# TCA0372_x.net
KiCad netlist of a schematic drawn in EAGLE
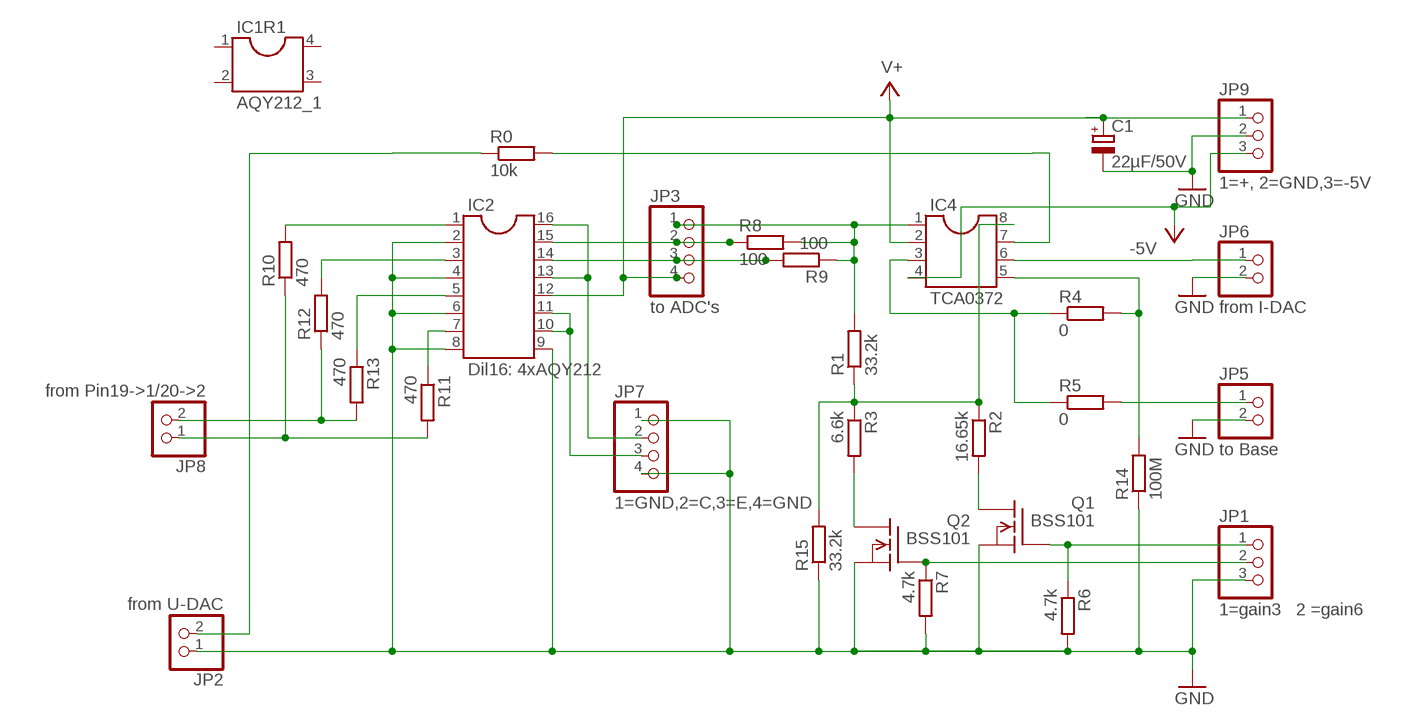
[diagram p0: schematic, sheet 1]

(export (version "E")
  (design (tool "Eeschema 10.0.6"))
  (components
    (comp (ref "C1")
      (value "22µF/50V")
      (footprint "eagle-import:E5-10,5")
      (libsource (lib "eagle-import") (part "CPOL-EUE5-10.5"))
    )
    (comp (ref "IC1R1")
      (value "AQY212_1")
      (footprint "eagle-import:SOCKET-04")
      (libsource (lib "eagle-import") (part "DIL4S"))
    )
    (comp (ref "IC2")
      (value "Dil16: 4xAQY212")
      (footprint "eagle-import:SOCKET-16")
      (libsource (lib "eagle-import") (part "DIL16S"))
    )
    (comp (ref "IC4")
      (value "TCA0372")
      (footprint "eagle-import:SOCKET-08")
      (libsource (lib "eagle-import") (part "DIL8S"))
    )
    (comp (ref "JP1")
      (value "1=gain3 2 =gain6")
      (footprint "eagle-import:1X03")
      (libsource (lib "eagle-import") (part "PINHD-1X3"))
    )
    (comp (ref "JP2")
      (value "from U-DAC")
      (footprint "eagle-import:1X02")
      (libsource (lib "eagle-import") (part "PINHD-1X2"))
    )
    (comp (ref "JP3")
      (value "to ADC's")
      (footprint "eagle-import:1X04")
      (libsource (lib "eagle-import") (part "PINHD-1X4"))
    )
    (comp (ref "JP5")
      (value "to Base")
      (footprint "eagle-import:1X02")
      (libsource (lib "eagle-import") (part "PINHD-1X2"))
    )
    (comp (ref "JP6")
      (value "from I-DAC")
      (footprint "eagle-import:1X02")
      (libsource (lib "eagle-import") (part "PINHD-1X2"))
    )
    (comp (ref "JP7")
      (value "1=GND,2=C,3=E,4=GND")
      (footprint "eagle-import:1X04")
      (libsource (lib "eagle-import") (part "PINHD-1X4"))
    )
    (comp (ref "JP8")
      (value "from Pin19->1/20->2")
      (footprint "eagle-import:1X02")
      (libsource (lib "eagle-import") (part "PINHD-1X2"))
    )
    (comp (ref "JP9")
      (value "1=+, 2=GND,3=-5V")
      (footprint "eagle-import:1X03")
      (libsource (lib "eagle-import") (part "PINHD-1X3"))
    )
    (comp (ref "Q1")
      (value "BSS101")
      (footprint "eagle-import:TO92")
      (libsource (lib "eagle-import") (part "BSS101"))
    )
    (comp (ref "Q2")
      (value "BSS101")
      (footprint "eagle-import:TO92")
      (libsource (lib "eagle-import") (part "BSS101"))
    )
    (comp (ref "R0")
      (value "10k")
      (footprint "eagle-import:0207_7")
      (libsource (lib "eagle-import") (part "R-EU_0207/7"))
    )
    (comp (ref "R1")
      (value "33.2k")
      (footprint "eagle-import:0207_7")
      (libsource (lib "eagle-import") (part "R-EU_0207/7"))
    )
    (comp (ref "R2")
      (value "16.65k")
      (footprint "eagle-import:0207_7")
      (libsource (lib "eagle-import") (part "R-EU_0207/7"))
    )
    (comp (ref "R3")
      (value "6.6k")
      (footprint "eagle-import:0207_7")
      (libsource (lib "eagle-import") (part "R-EU_0207/7"))
    )
    (comp (ref "R4")
      (value "0")
      (footprint "eagle-import:0207_7")
      (libsource (lib "eagle-import") (part "R-EU_0207/7"))
    )
    (comp (ref "R5")
      (value "0")
      (footprint "eagle-import:0207_7")
      (libsource (lib "eagle-import") (part "R-EU_0207/7"))
    )
    (comp (ref "R6")
      (value "4.7k")
      (footprint "eagle-import:0207_7")
      (libsource (lib "eagle-import") (part "R-EU_0207/7"))
    )
    (comp (ref "R7")
      (value "4.7k")
      (footprint "eagle-import:0207_7")
      (libsource (lib "eagle-import") (part "R-EU_0207/7"))
    )
    (comp (ref "R8")
      (value "100")
      (footprint "eagle-import:0207_7")
      (libsource (lib "eagle-import") (part "R-EU_0207/7"))
    )
    (comp (ref "R9")
      (value "100")
      (footprint "eagle-import:0207_7")
      (libsource (lib "eagle-import") (part "R-EU_0207/7"))
    )
    (comp (ref "R10")
      (value "470")
      (footprint "eagle-import:0207_7")
      (libsource (lib "eagle-import") (part "R-EU_0207/7"))
    )
    (comp (ref "R11")
      (value "470")
      (footprint "eagle-import:0207_7")
      (libsource (lib "eagle-import") (part "R-EU_0207/7"))
    )
    (comp (ref "R12")
      (value "470")
      (footprint "eagle-import:0207_7")
      (libsource (lib "eagle-import") (part "R-EU_0207/7"))
    )
    (comp (ref "R13")
      (value "470")
      (footprint "eagle-import:0207_7")
      (libsource (lib "eagle-import") (part "R-EU_0207/7"))
    )
    (comp (ref "R14")
      (value "100M")
      (footprint "eagle-import:0207_7")
      (libsource (lib "eagle-import") (part "R-EU_0207/7"))
    )
    (comp (ref "R15")
      (value "33.2k")
      (footprint "eagle-import:0207_7")
      (libsource (lib "eagle-import") (part "R-EU_0207/7"))
    )
  )
  (nets
    (net (code "1") (name "-5V") (class "Default")
      (node (ref "IC4") (pin "4") (pinfunction "4_4") (pintype "passive"))
      (node (ref "JP9") (pin "3") (pinfunction "3_3") (pintype "passive"))
    )
    (net (code "2") (name "GND") (class "Default")
      (node (ref "C1") (pin "-") (pinfunction "-_-") (pintype "passive"))
      (node (ref "IC2") (pin "2") (pinfunction "2_2") (pintype "passive"))
      (node (ref "IC2") (pin "4") (pinfunction "4_4") (pintype "passive"))
      (node (ref "IC2") (pin "6") (pinfunction "6_6") (pintype "passive"))
      (node (ref "IC2") (pin "8") (pinfunction "8_8") (pintype "passive"))
      (node (ref "IC2") (pin "9") (pinfunction "9_9") (pintype "passive"))
      (node (ref "JP1") (pin "3") (pinfunction "3_3") (pintype "passive"))
      (node (ref "JP2") (pin "1") (pinfunction "1_1") (pintype "passive"))
      (node (ref "JP5") (pin "2") (pinfunction "2_2") (pintype "passive"))
      (node (ref "JP6") (pin "2") (pinfunction "2_2") (pintype "passive"))
      (node (ref "JP7") (pin "1") (pinfunction "1_1") (pintype "passive"))
      (node (ref "JP7") (pin "4") (pinfunction "4_4") (pintype "passive"))
      (node (ref "JP9") (pin "2") (pinfunction "2_2") (pintype "passive"))
      (node (ref "Q1") (pin "1") (pinfunction "S_1") (pintype "passive"))
      (node (ref "Q2") (pin "1") (pinfunction "S_1") (pintype "passive"))
      (node (ref "R14") (pin "1") (pinfunction "1_1") (pintype "passive"))
      (node (ref "R15") (pin "1") (pinfunction "1_1") (pintype "passive"))
      (node (ref "R6") (pin "2") (pinfunction "2_2") (pintype "passive"))
      (node (ref "R7") (pin "2") (pinfunction "2_2") (pintype "passive"))
    )
    (net (code "3") (name "Net-(IC2-Pad1)") (class "Default")
      (node (ref "IC2") (pin "1") (pinfunction "1_1") (pintype "passive"))
      (node (ref "R10") (pin "2") (pinfunction "2_2") (pintype "passive"))
    )
    (net (code "4") (name "Net-(IC2-Pad3)") (class "Default")
      (node (ref "IC2") (pin "3") (pinfunction "3_3") (pintype "passive"))
      (node (ref "R12") (pin "2") (pinfunction "2_2") (pintype "passive"))
    )
    (net (code "5") (name "Net-(IC2-Pad5)") (class "Default")
      (node (ref "IC2") (pin "5") (pinfunction "5_5") (pintype "passive"))
      (node (ref "R13") (pin "1") (pinfunction "1_1") (pintype "passive"))
    )
    (net (code "6") (name "Net-(IC2-Pad7)") (class "Default")
      (node (ref "IC2") (pin "7") (pinfunction "7_7") (pintype "passive"))
      (node (ref "R11") (pin "1") (pinfunction "1_1") (pintype "passive"))
    )
    (net (code "7") (name "Net-(IC2-Pad10)") (class "Default")
      (node (ref "IC2") (pin "10") (pinfunction "10_10") (pintype "passive"))
      (node (ref "IC2") (pin "11") (pinfunction "11_11") (pintype "passive"))
      (node (ref "JP7") (pin "3") (pinfunction "3_3") (pintype "passive"))
    )
    (net (code "8") (name "Net-(IC2-Pad13)") (class "Default")
      (node (ref "IC2") (pin "13") (pinfunction "13_13") (pintype "passive"))
      (node (ref "IC2") (pin "16") (pinfunction "16_16") (pintype "passive"))
      (node (ref "JP7") (pin "2") (pinfunction "2_2") (pintype "passive"))
    )
    (net (code "9") (name "Net-(IC2-Pad14)") (class "Default")
      (node (ref "IC2") (pin "14") (pinfunction "14_14") (pintype "passive"))
      (node (ref "JP3") (pin "3") (pinfunction "3_3") (pintype "passive"))
      (node (ref "R9") (pin "2") (pinfunction "2_2") (pintype "passive"))
    )
    (net (code "10") (name "Net-(IC2-Pad15)") (class "Default")
      (node (ref "IC2") (pin "15") (pinfunction "15_15") (pintype "passive"))
      (node (ref "JP3") (pin "2") (pinfunction "2_2") (pintype "passive"))
      (node (ref "R8") (pin "1") (pinfunction "1_1") (pintype "passive"))
    )
    (net (code "11") (name "Net-(IC4-Pad1)") (class "Default")
      (node (ref "IC4") (pin "1") (pinfunction "1_1") (pintype "passive"))
      (node (ref "JP3") (pin "1") (pinfunction "1_1") (pintype "passive"))
      (node (ref "R1") (pin "2") (pinfunction "2_2") (pintype "passive"))
      (node (ref "R8") (pin "2") (pinfunction "2_2") (pintype "passive"))
      (node (ref "R9") (pin "1") (pinfunction "1_1") (pintype "passive"))
    )
    (net (code "12") (name "Net-(IC4-Pad3)") (class "Default")
      (node (ref "IC4") (pin "3") (pinfunction "3_3") (pintype "passive"))
      (node (ref "R4") (pin "1") (pinfunction "1_1") (pintype "passive"))
      (node (ref "R5") (pin "1") (pinfunction "1_1") (pintype "passive"))
    )
    (net (code "13") (name "Net-(IC4-Pad5)") (class "Default")
      (node (ref "IC4") (pin "5") (pinfunction "5_5") (pintype "passive"))
      (node (ref "R14") (pin "2") (pinfunction "2_2") (pintype "passive"))
      (node (ref "R4") (pin "2") (pinfunction "2_2") (pintype "passive"))
    )
    (net (code "14") (name "Net-(IC4-Pad6)") (class "Default")
      (node (ref "IC4") (pin "6") (pinfunction "6_6") (pintype "passive"))
      (node (ref "JP6") (pin "1") (pinfunction "1_1") (pintype "passive"))
    )
    (net (code "15") (name "Net-(IC4-Pad7)") (class "Default")
      (node (ref "IC4") (pin "7") (pinfunction "7_7") (pintype "passive"))
      (node (ref "R0") (pin "2") (pinfunction "2_2") (pintype "passive"))
    )
    (net (code "16") (name "Net-(IC4-Pad8)") (class "Default")
      (node (ref "IC4") (pin "8") (pinfunction "8_8") (pintype "passive"))
      (node (ref "R1") (pin "1") (pinfunction "1_1") (pintype "passive"))
      (node (ref "R15") (pin "2") (pinfunction "2_2") (pintype "passive"))
      (node (ref "R2") (pin "1") (pinfunction "1_1") (pintype "passive"))
      (node (ref "R3") (pin "1") (pinfunction "1_1") (pintype "passive"))
    )
    (net (code "17") (name "Net-(JP2-Pad2)") (class "Default")
      (node (ref "JP2") (pin "2") (pinfunction "2_2") (pintype "passive"))
      (node (ref "R0") (pin "1") (pinfunction "1_1") (pintype "passive"))
    )
    (net (code "18") (name "Net-(JP5-Pad1)") (class "Default")
      (node (ref "JP5") (pin "1") (pinfunction "1_1") (pintype "passive"))
      (node (ref "R5") (pin "2") (pinfunction "2_2") (pintype "passive"))
    )
    (net (code "19") (name "Net-(JP8-Pad1)") (class "Default")
      (node (ref "JP8") (pin "1") (pinfunction "1_1") (pintype "passive"))
      (node (ref "R10") (pin "1") (pinfunction "1_1") (pintype "passive"))
      (node (ref "R11") (pin "2") (pinfunction "2_2") (pintype "passive"))
    )
    (net (code "20") (name "Net-(JP8-Pad2)") (class "Default")
      (node (ref "JP8") (pin "2") (pinfunction "2_2") (pintype "passive"))
      (node (ref "R12") (pin "1") (pinfunction "1_1") (pintype "passive"))
      (node (ref "R13") (pin "2") (pinfunction "2_2") (pintype "passive"))
    )
    (net (code "21") (name "Net-(Q1-D)") (class "Default")
      (node (ref "Q1") (pin "3") (pinfunction "D_3") (pintype "passive"))
      (node (ref "R2") (pin "2") (pinfunction "2_2") (pintype "passive"))
    )
    (net (code "22") (name "Net-(Q1-G)") (class "Default")
      (node (ref "JP1") (pin "1") (pinfunction "1_1") (pintype "passive"))
      (node (ref "Q1") (pin "2") (pinfunction "G_2") (pintype "passive"))
      (node (ref "R6") (pin "1") (pinfunction "1_1") (pintype "passive"))
    )
    (net (code "23") (name "Net-(Q2-D)") (class "Default")
      (node (ref "Q2") (pin "3") (pinfunction "D_3") (pintype "passive"))
      (node (ref "R3") (pin "2") (pinfunction "2_2") (pintype "passive"))
    )
    (net (code "24") (name "Net-(Q2-G)") (class "Default")
      (node (ref "JP1") (pin "2") (pinfunction "2_2") (pintype "passive"))
      (node (ref "Q2") (pin "2") (pinfunction "G_2") (pintype "passive"))
      (node (ref "R7") (pin "1") (pinfunction "1_1") (pintype "passive"))
    )
    (net (code "25") (name "V+") (class "Default")
      (node (ref "C1") (pin "+") (pinfunction "+_+") (pintype "passive"))
      (node (ref "IC2") (pin "12") (pinfunction "12_12") (pintype "passive"))
      (node (ref "IC4") (pin "2") (pinfunction "2_2") (pintype "passive"))
      (node (ref "JP3") (pin "4") (pinfunction "4_4") (pintype "passive"))
      (node (ref "JP9") (pin "1") (pinfunction "1_1") (pintype "passive"))
    )
    (net (code "26") (name "unconnected-(IC1R1-Pad1)") (class "Default")
      (node (ref "IC1R1") (pin "1") (pinfunction "1_1") (pintype "passive"))
    )
    (net (code "27") (name "unconnected-(IC1R1-Pad2)") (class "Default")
      (node (ref "IC1R1") (pin "2") (pinfunction "2_2") (pintype "passive"))
    )
    (net (code "28") (name "unconnected-(IC1R1-Pad3)") (class "Default")
      (node (ref "IC1R1") (pin "3") (pinfunction "3_3") (pintype "passive"))
    )
    (net (code "29") (name "unconnected-(IC1R1-Pad4)") (class "Default")
      (node (ref "IC1R1") (pin "4") (pinfunction "4_4") (pintype "passive"))
    )
  )
)
